# OnOnfre_DevBoard.net
KiCad netlist of a schematic drawn in EAGLE
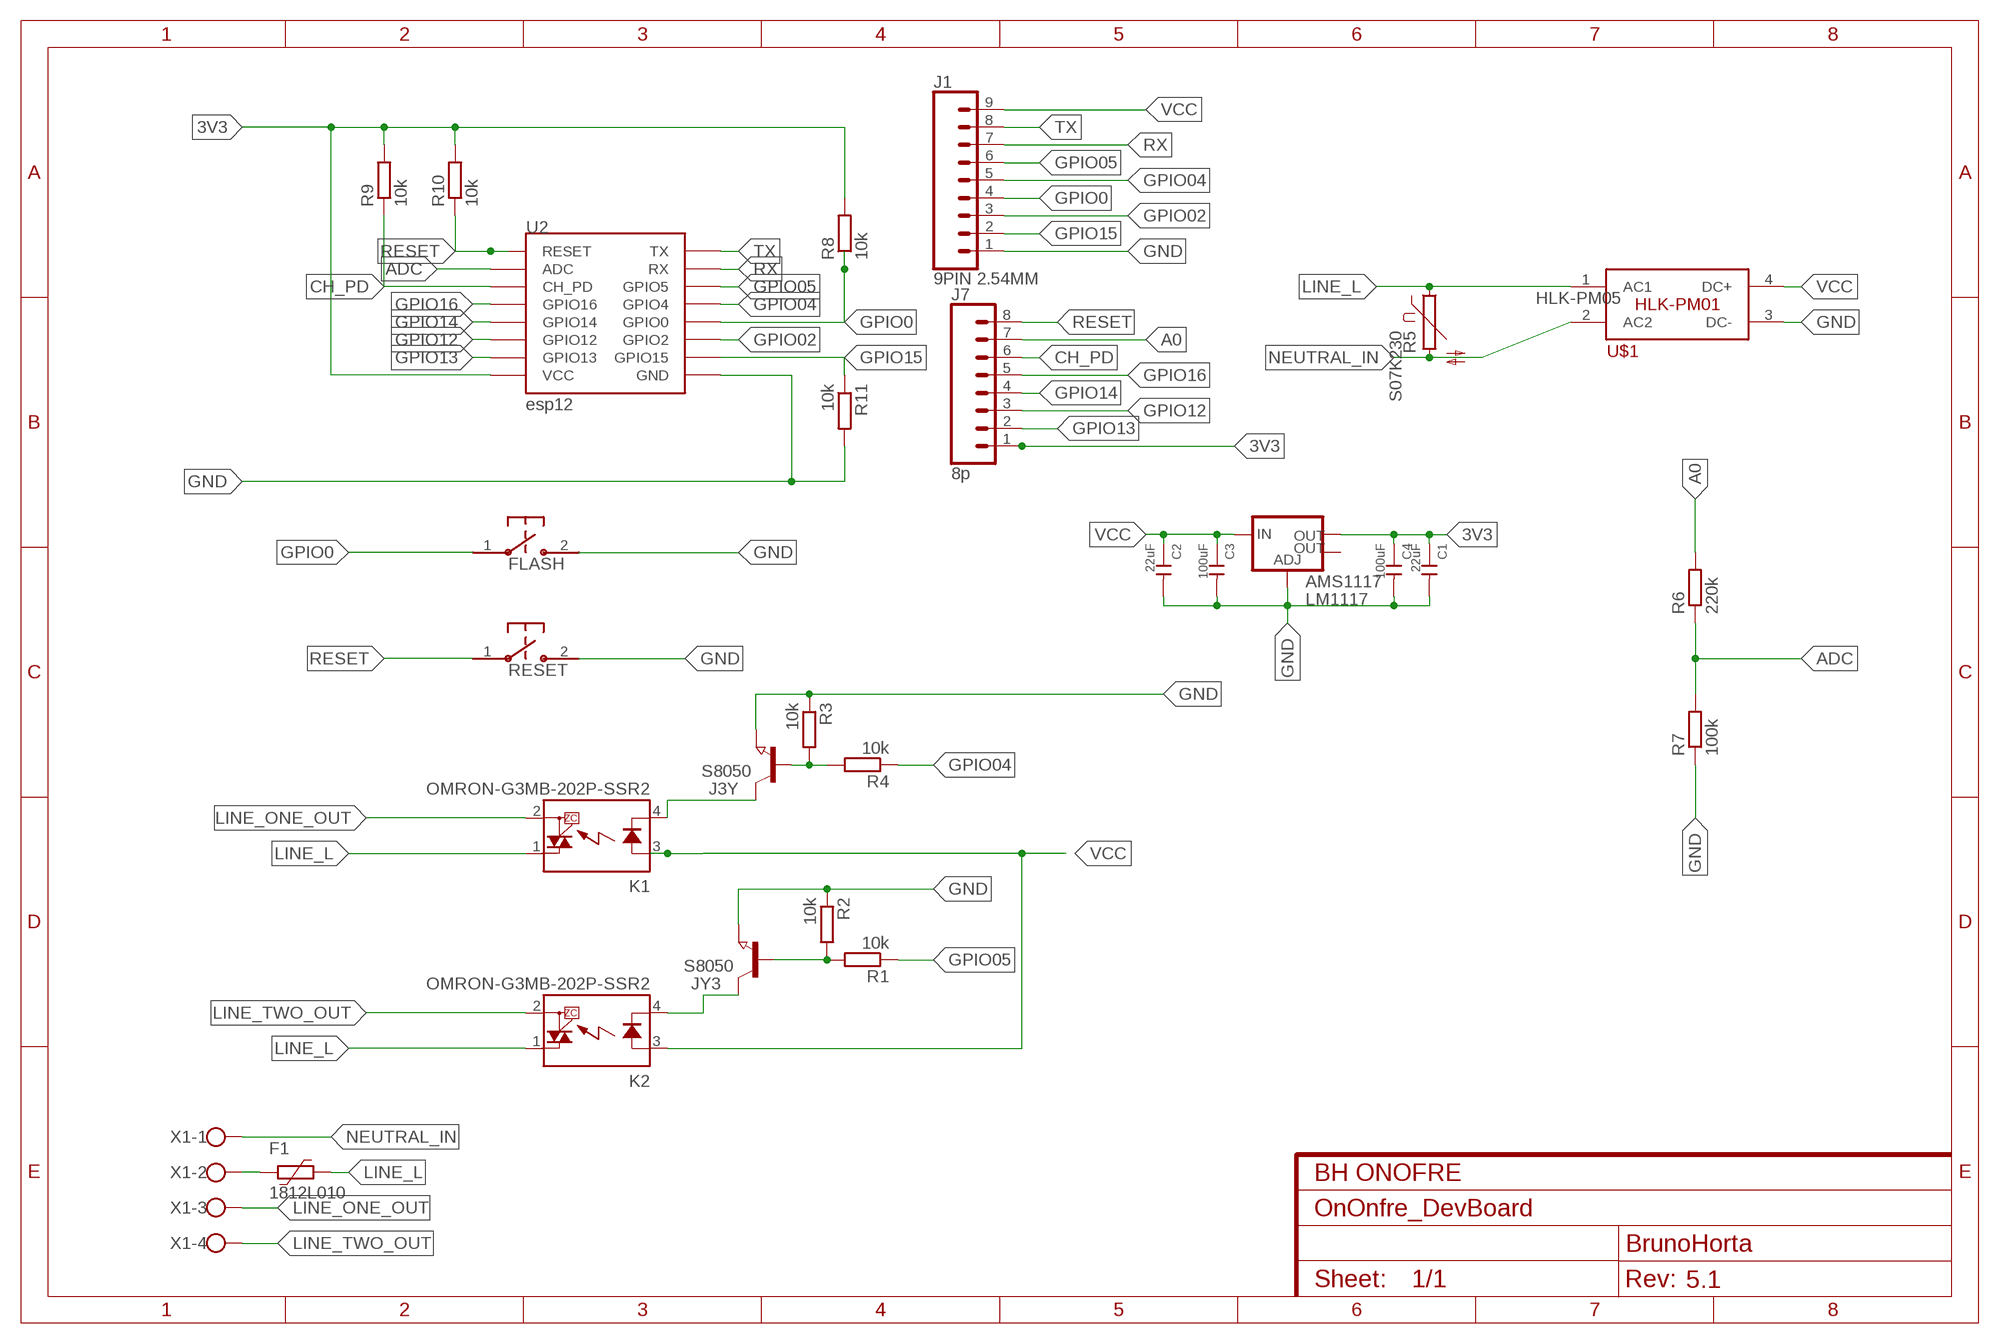
[diagram p0: schematic, sheet 1]

(export (version "E")
  (design (tool "Eeschema 10.0.6"))
  (components
    (comp (ref "AMS1117")
      (value "LM1117")
      (footprint "eagle-import:SOT223")
      (libsource (lib "eagle-import") (part "V_REG_LM1117SOT223"))
    )
    (comp (ref "C1")
      (value "22uF")
      (footprint "eagle-import:C1206")
      (fields (field (name "MPN") "CC1206KKX7RCBB102"))
      (libsource (lib "eagle-import") (part "CERAMIC-1NF-1KV-10%-X7R?(1206)"))
    )
    (comp (ref "C2")
      (value "22uF")
      (footprint "eagle-import:C1206")
      (fields (field (name "MPN") "CC1206KKX7RCBB102"))
      (libsource (lib "eagle-import") (part "CERAMIC-1NF-1KV-10%-X7R?(1206)"))
    )
    (comp (ref "C3")
      (value "100uF")
      (footprint "eagle-import:C1206")
      (fields (field (name "MPN") "CC1206KKX7RCBB102"))
      (libsource (lib "eagle-import") (part "CERAMIC-1NF-1KV-10%-X7R?(1206)"))
    )
    (comp (ref "C4")
      (value "100uF")
      (footprint "eagle-import:C1206")
      (fields (field (name "MPN") "CC1206KKX7RCBB102"))
      (libsource (lib "eagle-import") (part "CERAMIC-1NF-1KV-10%-X7R?(1206)"))
    )
    (comp (ref "F1")
      (value "1812L010")
      (footprint "eagle-import:1812L")
      (fields (field (name "MF") "Littelfuse"))
      (libsource (lib "eagle-import") (part "?1812L010"))
    )
    (comp (ref "FLASH")
      (value "B3U-1000P-2P-SMD")
      (footprint "eagle-import:B3U-1000P")
      (fields (field (name "MANUFACTURER") "Omron") (field (name "MPN") "B3U-1000P"))
      (libsource (lib "eagle-import") (part "B3U-1000P"))
    )
    (comp (ref "J1")
      (value "9PIN 2.54MM")
      (footprint "eagle-import:1X09")
      (libsource (lib "eagle-import") (part "CONN_09"))
    )
    (comp (ref "J3Y")
      (value "S8050")
      (footprint "eagle-import:SOT23")
      (libsource (lib "eagle-import") (part "NPN-TRANSISTOR_SOT23"))
    )
    (comp (ref "J7")
      (value "8p")
      (footprint "eagle-import:1X08")
      (libsource (lib "eagle-import") (part "CONN_08{dblquote}"))
    )
    (comp (ref "JY3")
      (value "S8050")
      (footprint "eagle-import:SOT23")
      (libsource (lib "eagle-import") (part "NPN-TRANSISTOR_SOT23"))
    )
    (comp (ref "K1")
      (value "OMRON-G3MB-202P-SSR2")
      (footprint "eagle-import:OMRON-G3MB-202P-SSR")
      (fields (field (name "MPN") "S202S02F"))
      (libsource (lib "eagle-import") (part "OMRON-G3MB-202P-SSR2"))
    )
    (comp (ref "K2")
      (value "OMRON-G3MB-202P-SSR2")
      (footprint "eagle-import:OMRON-G3MB-202P-SSR")
      (fields (field (name "MPN") "S202S02F"))
      (libsource (lib "eagle-import") (part "OMRON-G3MB-202P-SSR2"))
    )
    (comp (ref "R1")
      (value "10k")
      (footprint "eagle-import:R0603")
      (libsource (lib "eagle-import") (part "R-EU_R0603"))
    )
    (comp (ref "R2")
      (value "10k")
      (footprint "eagle-import:R0603")
      (libsource (lib "eagle-import") (part "R-EU_R0603"))
    )
    (comp (ref "R3")
      (value "10k")
      (footprint "eagle-import:R0603")
      (libsource (lib "eagle-import") (part "R-EU_R0603"))
    )
    (comp (ref "R4")
      (value "10k")
      (footprint "eagle-import:R0603")
      (libsource (lib "eagle-import") (part "R-EU_R0603"))
    )
    (comp (ref "R5")
      (value "S07K230")
      (footprint "eagle-import:S07K230")
      (libsource (lib "eagle-import") (part "S07K230"))
    )
    (comp (ref "R6")
      (value "220k")
      (footprint "eagle-import:R0603")
      (libsource (lib "eagle-import") (part "R-EU_R0603"))
    )
    (comp (ref "R7")
      (value "100k")
      (footprint "eagle-import:R0603")
      (libsource (lib "eagle-import") (part "R-EU_R0603"))
    )
    (comp (ref "R8")
      (value "10k")
      (footprint "eagle-import:R0603")
      (libsource (lib "eagle-import") (part "R-EU_R0603"))
    )
    (comp (ref "R9")
      (value "10k")
      (footprint "eagle-import:R0603")
      (libsource (lib "eagle-import") (part "R-EU_R0603"))
    )
    (comp (ref "R10")
      (value "10k")
      (footprint "eagle-import:R0603")
      (libsource (lib "eagle-import") (part "R-EU_R0603"))
    )
    (comp (ref "R11")
      (value "10k")
      (footprint "eagle-import:R0603")
      (libsource (lib "eagle-import") (part "R-EU_R0603"))
    )
    (comp (ref "RESET")
      (value "B3U-1000P-2P-SMD")
      (footprint "eagle-import:B3U-1000P")
      (fields (field (name "MANUFACTURER") "Omron") (field (name "MPN") "B3U-1000P"))
      (libsource (lib "eagle-import") (part "B3U-1000P"))
    )
    (comp (ref "U$1")
      (value "HLK-PM01")
      (footprint "eagle-import:HLK-PM01")
      (fields (field (name "MF") "Hi-link") (field (name "MP") "hlk-pm01"))
      (libsource (lib "eagle-import") (part "HLK-PM01"))
    )
    (comp (ref "U2")
      (value "esp12")
      (footprint "eagle-import:ESP12-SMD")
      (libsource (lib "eagle-import") (part "ESP12SMD"))
    )
    (comp (ref "X1")
      (value "W237-4")
      (footprint "eagle-import:W237-4")
      (libsource (lib "eagle-import") (part "W237-4"))
    )
  )
  (nets
    (net (code "1") (name "3V3") (class "Default")
      (node (ref "AMS1117") (pin "2") (pinfunction "OUT_2") (pintype "output"))
      (node (ref "C1") (pin "1") (pinfunction "1_1") (pintype "passive"))
      (node (ref "C4") (pin "1") (pinfunction "1_1") (pintype "passive"))
      (node (ref "J7") (pin "1") (pinfunction "1_1") (pintype "passive"))
      (node (ref "R10") (pin "2") (pinfunction "2_2") (pintype "passive"))
      (node (ref "R8") (pin "2") (pinfunction "2_2") (pintype "passive"))
      (node (ref "R9") (pin "2") (pinfunction "2_2") (pintype "passive"))
      (node (ref "U2") (pin "VCC") (pinfunction "VCC_VCC") (pintype "bidirectional"))
    )
    (net (code "2") (name "A0") (class "Default")
      (node (ref "J7") (pin "7") (pinfunction "7_7") (pintype "passive"))
      (node (ref "R6") (pin "2") (pinfunction "2_2") (pintype "passive"))
    )
    (net (code "3") (name "ADC") (class "Default")
      (node (ref "R6") (pin "1") (pinfunction "1_1") (pintype "passive"))
      (node (ref "R7") (pin "2") (pinfunction "2_2") (pintype "passive"))
      (node (ref "U2") (pin "ADC") (pinfunction "ADC_ADC") (pintype "bidirectional"))
    )
    (net (code "4") (name "CH_PD") (class "Default")
      (node (ref "J7") (pin "6") (pinfunction "6_6") (pintype "passive"))
      (node (ref "R9") (pin "1") (pinfunction "1_1") (pintype "passive"))
      (node (ref "U2") (pin "CH_PD") (pinfunction "CH_PD_CH_PD") (pintype "bidirectional"))
    )
    (net (code "5") (name "GND") (class "Default")
      (node (ref "AMS1117") (pin "1") (pinfunction "ADJ_1") (pintype "input"))
      (node (ref "C1") (pin "2") (pinfunction "2_2") (pintype "passive"))
      (node (ref "C2") (pin "2") (pinfunction "2_2") (pintype "passive"))
      (node (ref "C3") (pin "2") (pinfunction "2_2") (pintype "passive"))
      (node (ref "C4") (pin "2") (pinfunction "2_2") (pintype "passive"))
      (node (ref "FLASH") (pin "2") (pinfunction "P$2_2") (pintype "passive"))
      (node (ref "J1") (pin "1") (pinfunction "1_1") (pintype "passive"))
      (node (ref "J3Y") (pin "2") (pinfunction "E_2") (pintype "passive"))
      (node (ref "JY3") (pin "2") (pinfunction "E_2") (pintype "passive"))
      (node (ref "R11") (pin "2") (pinfunction "2_2") (pintype "passive"))
      (node (ref "R2") (pin "1") (pinfunction "1_1") (pintype "passive"))
      (node (ref "R3") (pin "1") (pinfunction "1_1") (pintype "passive"))
      (node (ref "R7") (pin "1") (pinfunction "1_1") (pintype "passive"))
      (node (ref "RESET") (pin "2") (pinfunction "P$2_2") (pintype "passive"))
      (node (ref "U$1") (pin "3") (pinfunction "DC-_3") (pintype "power_in"))
      (node (ref "U2") (pin "GND") (pinfunction "GND_GND") (pintype "bidirectional"))
    )
    (net (code "6") (name "GPIO0") (class "Default")
      (node (ref "FLASH") (pin "1") (pinfunction "P$1_1") (pintype "passive"))
      (node (ref "J1") (pin "4") (pinfunction "4_4") (pintype "passive"))
      (node (ref "R8") (pin "1") (pinfunction "1_1") (pintype "passive"))
      (node (ref "U2") (pin "GPIO0") (pinfunction "GPIO0_GPIO0") (pintype "bidirectional"))
    )
    (net (code "7") (name "GPIO02") (class "Default")
      (node (ref "J1") (pin "3") (pinfunction "3_3") (pintype "passive"))
      (node (ref "U2") (pin "GPIO2") (pinfunction "GPIO2_GPIO2") (pintype "bidirectional"))
    )
    (net (code "8") (name "GPIO04") (class "Default")
      (node (ref "J1") (pin "5") (pinfunction "5_5") (pintype "passive"))
      (node (ref "R4") (pin "1") (pinfunction "1_1") (pintype "passive"))
      (node (ref "U2") (pin "GPIO4") (pinfunction "GPIO4_GPIO4") (pintype "bidirectional"))
    )
    (net (code "9") (name "GPIO05") (class "Default")
      (node (ref "J1") (pin "6") (pinfunction "6_6") (pintype "passive"))
      (node (ref "R1") (pin "1") (pinfunction "1_1") (pintype "passive"))
      (node (ref "U2") (pin "GPIO5") (pinfunction "GPIO5_GPIO5") (pintype "bidirectional"))
    )
    (net (code "10") (name "GPIO12") (class "Default")
      (node (ref "J7") (pin "3") (pinfunction "3_3") (pintype "passive"))
      (node (ref "U2") (pin "GPIO12") (pinfunction "GPIO12_GPIO12") (pintype "bidirectional"))
    )
    (net (code "11") (name "GPIO13") (class "Default")
      (node (ref "J7") (pin "2") (pinfunction "2_2") (pintype "passive"))
      (node (ref "U2") (pin "GPIO13") (pinfunction "GPIO13_GPIO13") (pintype "bidirectional"))
    )
    (net (code "12") (name "GPIO14") (class "Default")
      (node (ref "J7") (pin "4") (pinfunction "4_4") (pintype "passive"))
      (node (ref "U2") (pin "GPIO14") (pinfunction "GPIO14_GPIO14") (pintype "bidirectional"))
    )
    (net (code "13") (name "GPIO15") (class "Default")
      (node (ref "J1") (pin "2") (pinfunction "2_2") (pintype "passive"))
      (node (ref "R11") (pin "1") (pinfunction "1_1") (pintype "passive"))
      (node (ref "U2") (pin "GPIO15") (pinfunction "GPIO15_GPIO15") (pintype "bidirectional"))
    )
    (net (code "14") (name "GPIO16") (class "Default")
      (node (ref "J7") (pin "5") (pinfunction "5_5") (pintype "passive"))
      (node (ref "U2") (pin "GPIO16") (pinfunction "GPIO16_GPIO16") (pintype "bidirectional"))
    )
    (net (code "15") (name "LINE_L") (class "Default")
      (node (ref "F1") (pin "1") (pinfunction "1_1") (pintype "passive"))
      (node (ref "K1") (pin "1") (pinfunction "DS1_1") (pintype "passive"))
      (node (ref "K2") (pin "1") (pinfunction "DS1_1") (pintype "passive"))
      (node (ref "R5") (pin "1") (pinfunction "1_1") (pintype "passive"))
      (node (ref "U$1") (pin "1") (pinfunction "AC1_1") (pintype "power_in"))
    )
    (net (code "16") (name "LINE_ONE_OUT") (class "Default")
      (node (ref "K1") (pin "2") (pinfunction "DS2_2") (pintype "passive"))
      (node (ref "X1") (pin "3") (pinfunction "KL_3") (pintype "passive"))
    )
    (net (code "17") (name "LINE_TWO_OUT") (class "Default")
      (node (ref "K2") (pin "2") (pinfunction "DS2_2") (pintype "passive"))
      (node (ref "X1") (pin "4") (pinfunction "KL_4") (pintype "passive"))
    )
    (net (code "18") (name "NEUTRAL_IN") (class "Default")
      (node (ref "R5") (pin "2") (pinfunction "2_2") (pintype "passive"))
      (node (ref "U$1") (pin "2") (pinfunction "AC2_2") (pintype "power_in"))
      (node (ref "X1") (pin "1") (pinfunction "KL_1") (pintype "passive"))
    )
    (net (code "19") (name "Net-(J3Y-B)") (class "Default")
      (node (ref "J3Y") (pin "1") (pinfunction "B_1") (pintype "passive"))
      (node (ref "R3") (pin "2") (pinfunction "2_2") (pintype "passive"))
      (node (ref "R4") (pin "2") (pinfunction "2_2") (pintype "passive"))
    )
    (net (code "20") (name "Net-(J3Y-C)") (class "Default")
      (node (ref "J3Y") (pin "3") (pinfunction "C_3") (pintype "passive"))
      (node (ref "K1") (pin "4") (pinfunction "K_4") (pintype "passive"))
    )
    (net (code "21") (name "Net-(JY3-B)") (class "Default")
      (node (ref "JY3") (pin "1") (pinfunction "B_1") (pintype "passive"))
      (node (ref "R1") (pin "2") (pinfunction "2_2") (pintype "passive"))
      (node (ref "R2") (pin "2") (pinfunction "2_2") (pintype "passive"))
    )
    (net (code "22") (name "Net-(JY3-C)") (class "Default")
      (node (ref "JY3") (pin "3") (pinfunction "C_3") (pintype "passive"))
      (node (ref "K2") (pin "4") (pinfunction "K_4") (pintype "passive"))
    )
    (net (code "23") (name "Net-(X1B-KL)") (class "Default")
      (node (ref "F1") (pin "2") (pinfunction "2_2") (pintype "passive"))
      (node (ref "X1") (pin "2") (pinfunction "KL_2") (pintype "passive"))
    )
    (net (code "24") (name "RESET") (class "Default")
      (node (ref "J7") (pin "8") (pinfunction "8_8") (pintype "passive"))
      (node (ref "R10") (pin "1") (pinfunction "1_1") (pintype "passive"))
      (node (ref "RESET") (pin "1") (pinfunction "P$1_1") (pintype "passive"))
      (node (ref "U2") (pin "RESET") (pinfunction "RESET_RESET") (pintype "bidirectional"))
    )
    (net (code "25") (name "RX") (class "Default")
      (node (ref "J1") (pin "7") (pinfunction "7_7") (pintype "passive"))
      (node (ref "U2") (pin "RXD0") (pinfunction "RX_RXD0") (pintype "bidirectional"))
    )
    (net (code "26") (name "TX") (class "Default")
      (node (ref "J1") (pin "8") (pinfunction "8_8") (pintype "passive"))
      (node (ref "U2") (pin "TXD0") (pinfunction "TX_TXD0") (pintype "bidirectional"))
    )
    (net (code "27") (name "VCC") (class "Default")
      (node (ref "AMS1117") (pin "3") (pinfunction "IN_3") (pintype "input"))
      (node (ref "C2") (pin "1") (pinfunction "1_1") (pintype "passive"))
      (node (ref "C3") (pin "1") (pinfunction "1_1") (pintype "passive"))
      (node (ref "J1") (pin "9") (pinfunction "9_9") (pintype "passive"))
      (node (ref "K1") (pin "3") (pinfunction "A_3") (pintype "passive"))
      (node (ref "K2") (pin "3") (pinfunction "A_3") (pintype "passive"))
      (node (ref "U$1") (pin "4") (pinfunction "DC+_4") (pintype "power_in"))
    )
    (net (code "28") (name "unconnected-(AMS1117-OUT-Pad4)") (class "Default")
      (node (ref "AMS1117") (pin "4") (pinfunction "OUT_4") (pintype "output"))
    )
  )
)
